# Sheet1.net
KiCad netlist of a schematic drawn in Altium Designer
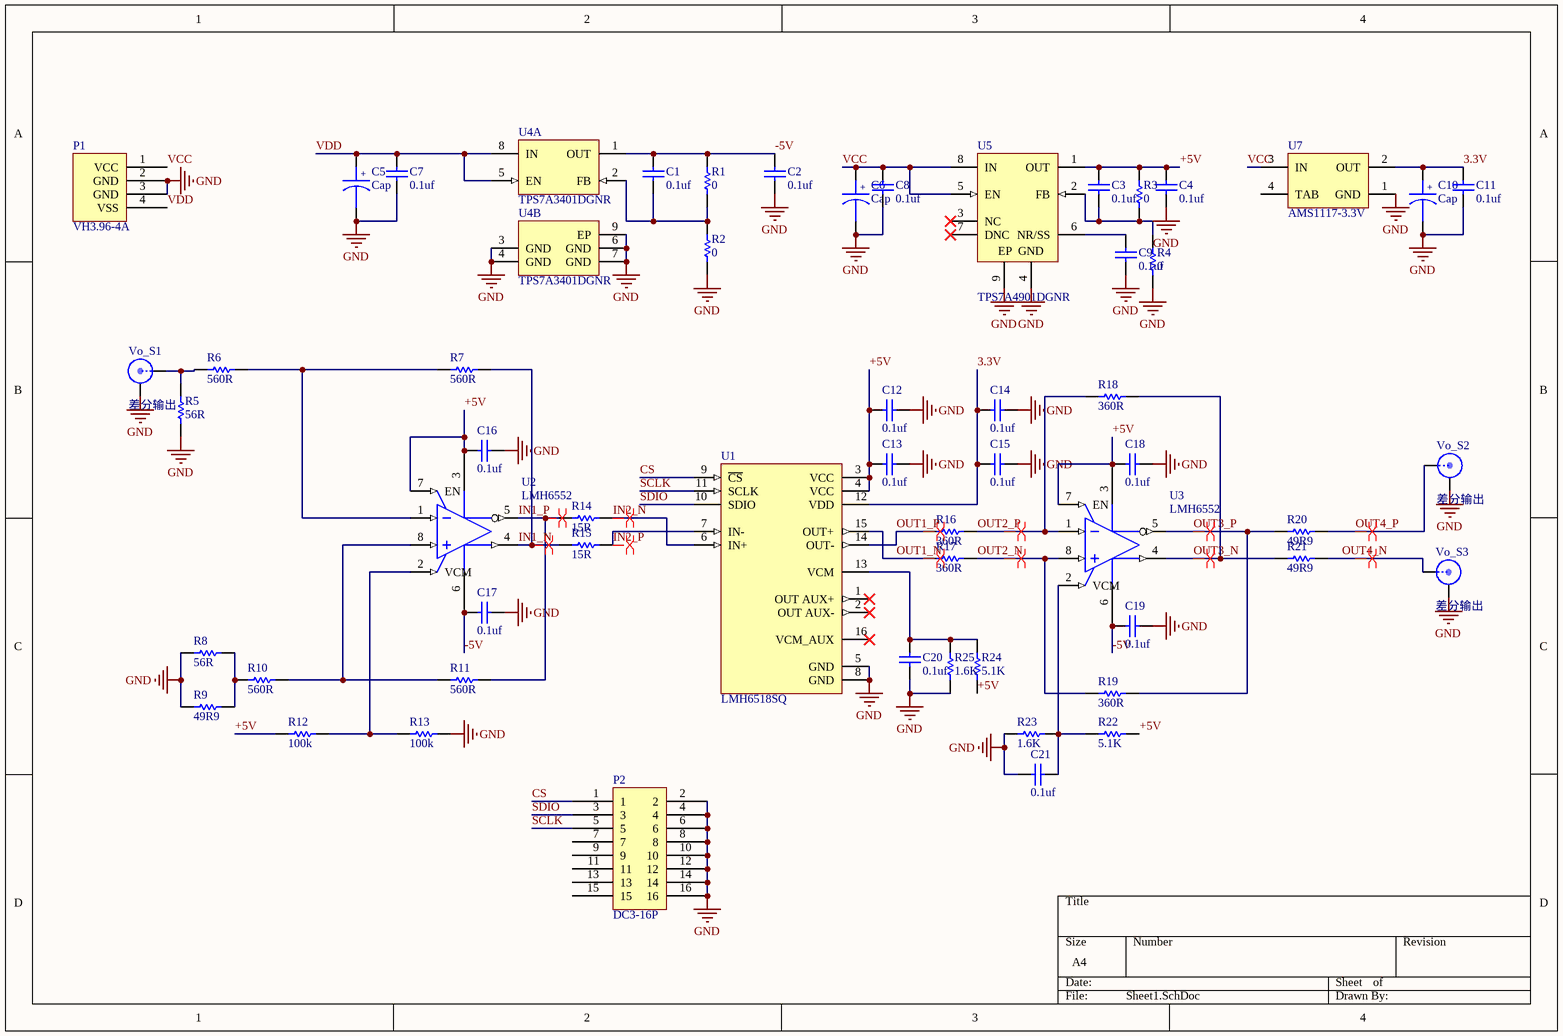
[diagram p0: Sheet1.SchDoc]

(export (version "E")
  (design (tool "Eeschema 10.0.6"))
  (components
    (comp (ref "C1") (value "0.1uf") (footprint "0805") (libsource (lib "Schlib1") (part "Cap")))
    (comp (ref "C2") (value "0.1uf") (footprint "0805") (libsource (lib "Schlib1") (part "Cap")))
    (comp (ref "C3") (value "0.1uf") (footprint "0805") (libsource (lib "Schlib1") (part "Cap")))
    (comp (ref "C4") (value "0.1uf") (footprint "0805") (libsource (lib "Schlib1") (part "Cap")))
    (comp (ref "C5")
      (value "Cap")
      (footprint "7343C-TYPE_D")
      (libsource (lib "Schlib1") (part "Tantalium Cap"))
    )
    (comp (ref "C6")
      (value "Cap")
      (footprint "7343C-TYPE_D")
      (libsource (lib "Schlib1") (part "Tantalium Cap"))
    )
    (comp (ref "C7") (value "0.1uf") (footprint "0805") (libsource (lib "Schlib1") (part "Cap")))
    (comp (ref "C8") (value "0.1uf") (footprint "0805") (libsource (lib "Schlib1") (part "Cap")))
    (comp (ref "C9") (value "0.1uf") (footprint "0805") (libsource (lib "Schlib1") (part "Cap")))
    (comp (ref "C10")
      (value "Cap")
      (footprint "3216C-TYPE_A")
      (libsource (lib "Schlib1") (part "Tantalium Cap"))
    )
    (comp (ref "C11") (value "0.1uf") (footprint "0805") (libsource (lib "Schlib1") (part "Cap")))
    (comp (ref "C12") (value "0.1uf") (footprint "0603C") (libsource (lib "Schlib1") (part "Cap")))
    (comp (ref "C13") (value "0.1uf") (footprint "0603C") (libsource (lib "Schlib1") (part "Cap")))
    (comp (ref "C14") (value "0.1uf") (footprint "0603C") (libsource (lib "Schlib1") (part "Cap")))
    (comp (ref "C15") (value "0.1uf") (footprint "0603C") (libsource (lib "Schlib1") (part "Cap")))
    (comp (ref "C16") (value "0.1uf") (footprint "0805") (libsource (lib "Schlib1") (part "Cap")))
    (comp (ref "C17") (value "0.1uf") (footprint "0805") (libsource (lib "Schlib1") (part "Cap")))
    (comp (ref "C18") (value "0.1uf") (footprint "0805") (libsource (lib "Schlib1") (part "Cap")))
    (comp (ref "C19") (value "0.1uf") (footprint "0805") (libsource (lib "Schlib1") (part "Cap")))
    (comp (ref "C20") (value "0.1uf") (footprint "0603C") (libsource (lib "Schlib1") (part "Cap")))
    (comp (ref "C21") (value "0.1uf") (footprint "0603C") (libsource (lib "Schlib1") (part "Cap")))
    (comp (ref "P1")
      (value "VH3.96-4A")
      (footprint "VH3.96-4P")
      (libsource (lib "Schlib1") (part "VH3.96-4A"))
    )
    (comp (ref "P2") (value "DC3-16P") (footprint "DC3-14P") (libsource (lib "Schlib1") (part "DC3-16P")))
    (comp (ref "R1") (value "0") (footprint "0805") (libsource (lib "Schlib1") (part "Res")))
    (comp (ref "R2") (value "0") (footprint "0805") (libsource (lib "Schlib1") (part "Res")))
    (comp (ref "R3") (value "0") (footprint "0805") (libsource (lib "Schlib1") (part "Res")))
    (comp (ref "R4") (value "0") (footprint "0805") (libsource (lib "Schlib1") (part "Res")))
    (comp (ref "R5") (value "56R") (footprint "0603R") (libsource (lib "Schlib1") (part "Res")))
    (comp (ref "R6") (value "560R") (footprint "0603R") (libsource (lib "Schlib1") (part "Res")))
    (comp (ref "R7") (value "560R") (footprint "0603R") (libsource (lib "Schlib1") (part "Res")))
    (comp (ref "R8") (value "56R") (footprint "0603R") (libsource (lib "Schlib1") (part "Res")))
    (comp (ref "R9") (value "49R9") (footprint "0603R") (libsource (lib "Schlib1") (part "Res")))
    (comp (ref "R10") (value "560R") (footprint "0603R") (libsource (lib "Schlib1") (part "Res")))
    (comp (ref "R11") (value "560R") (footprint "0603R") (libsource (lib "Schlib1") (part "Res")))
    (comp (ref "R12") (value "100k") (footprint "0603R") (libsource (lib "Schlib1") (part "Res")))
    (comp (ref "R13") (value "100k") (footprint "0603R") (libsource (lib "Schlib1") (part "Res")))
    (comp (ref "R14") (value "15R") (footprint "0603R") (libsource (lib "Schlib1") (part "Res")))
    (comp (ref "R15") (value "15R") (footprint "0603R") (libsource (lib "Schlib1") (part "Res")))
    (comp (ref "R16") (value "360R") (footprint "0603R") (libsource (lib "Schlib1") (part "Res")))
    (comp (ref "R17") (value "360R") (footprint "0603R") (libsource (lib "Schlib1") (part "Res")))
    (comp (ref "R18") (value "360R") (footprint "0603R") (libsource (lib "Schlib1") (part "Res")))
    (comp (ref "R19") (value "360R") (footprint "0603R") (libsource (lib "Schlib1") (part "Res")))
    (comp (ref "R20") (value "49R9") (footprint "0603R") (libsource (lib "Schlib1") (part "Res")))
    (comp (ref "R21") (value "49R9") (footprint "0603R") (libsource (lib "Schlib1") (part "Res")))
    (comp (ref "R22") (value "5.1K") (footprint "0603R") (libsource (lib "Schlib1") (part "Res")))
    (comp (ref "R23") (value "1.6K") (footprint "0603R") (libsource (lib "Schlib1") (part "Res")))
    (comp (ref "R24") (value "5.1K") (footprint "0603R") (libsource (lib "Schlib1") (part "Res")))
    (comp (ref "R25") (value "1.6K") (footprint "0603R") (libsource (lib "Schlib1") (part "Res")))
    (comp (ref "U1")
      (value "LMH6518SQ")
      (footprint "SQA16A")
      (description "900 MHz, Digitally Controlled, Variable Gain Amplifier, 16-pin LLP")
      (fields (field (name "PARTNUMBER") "LMH6518") (field (name "MANUFACTURER") "National Semiconductor"))
      (libsource (lib "Schlib1") (part "LMH6518SQ"))
    )
    (comp (ref "U2") (value "LMH6552") (footprint "TI-D8_M") (libsource (lib "Schlib1") (part "LMH6552")))
    (comp (ref "U3") (value "LMH6552") (footprint "TI-D8_M") (libsource (lib "Schlib1") (part "LMH6552")))
    (comp (ref "U4")
      (value "TPS7A3401DGNR")
      (footprint "TI-DGN8-1760X1425TP_N")
      (fields (field (name "MANUFACTURER") "Texas Instruments"))
      (libsource (lib "Schlib1") (part "TPS7A3401DGNR"))
    )
    (comp (ref "U5")
      (value "TPS7A4901DGNR")
      (footprint "TI-DGN8-1760X1425TP_L")
      (fields (field (name "MANUFACTURER") "Texas Instruments"))
      (libsource (lib "Schlib1") (part "TPS7A4901DGNR"))
    )
    (comp (ref "U7")
      (value "AMS1117-3.3V")
      (footprint "SOT-223")
      (libsource (lib "Schlib1") (part "AMS1117-3.3V"))
    )
    (comp (ref "Vo_S1") (value "差分输出") (footprint "SMA-LYING") (libsource (lib "Schlib1") (part "SMA")))
    (comp (ref "Vo_S2") (value "差分输出") (footprint "SMA-LYING") (libsource (lib "Schlib1") (part "SMA")))
    (comp (ref "Vo_S3") (value "差分输出") (footprint "SMA-LYING") (libsource (lib "Schlib1") (part "SMA")))
  )
  (nets
    (net (code "1") (name "/+5V") (class "Default")
      (node (ref "C12") (pin "1") (pinfunction "1_1") (pintype "passive"))
      (node (ref "C13") (pin "1") (pinfunction "1_1") (pintype "passive"))
      (node (ref "C16") (pin "1") (pinfunction "1_1") (pintype "passive"))
      (node (ref "C18") (pin "2") (pinfunction "2_2") (pintype "passive"))
      (node (ref "C3") (pin "2") (pinfunction "2_2") (pintype "passive"))
      (node (ref "C4") (pin "2") (pinfunction "2_2") (pintype "passive"))
      (node (ref "R12") (pin "2") (pinfunction "2_2") (pintype "passive"))
      (node (ref "R22") (pin "1") (pinfunction "1_1") (pintype "passive"))
      (node (ref "R24") (pin "2") (pinfunction "2_2") (pintype "passive"))
      (node (ref "R3") (pin "2") (pinfunction "2_2") (pintype "passive"))
      (node (ref "U1") (pin "3") (pinfunction "VCC_3") (pintype "power_in"))
      (node (ref "U1") (pin "4") (pinfunction "VCC_4") (pintype "power_in"))
      (node (ref "U2") (pin "3") (pinfunction "VCC_3") (pintype "passive"))
      (node (ref "U2") (pin "7") (pinfunction "EN_7") (pintype "input"))
      (node (ref "U3") (pin "3") (pinfunction "VCC_3") (pintype "passive"))
      (node (ref "U3") (pin "7") (pinfunction "EN_7") (pintype "input"))
      (node (ref "U5") (pin "1") (pinfunction "OUT_1") (pintype "power_in"))
    )
    (net (code "2") (name "/-5V") (class "Default")
      (node (ref "C1") (pin "2") (pinfunction "2_2") (pintype "passive"))
      (node (ref "C17") (pin "1") (pinfunction "1_1") (pintype "passive"))
      (node (ref "C19") (pin "2") (pinfunction "2_2") (pintype "passive"))
      (node (ref "C2") (pin "2") (pinfunction "2_2") (pintype "passive"))
      (node (ref "R1") (pin "2") (pinfunction "2_2") (pintype "passive"))
      (node (ref "U2") (pin "6") (pinfunction "VDD_6") (pintype "passive"))
      (node (ref "U3") (pin "6") (pinfunction "VDD_6") (pintype "passive"))
      (node (ref "U4") (pin "1") (pinfunction "OUT_1") (pintype "power_in"))
    )
    (net (code "3") (name "/3.3V") (class "Default")
      (node (ref "C10") (pin "1") (pinfunction "1_1") (pintype "passive"))
      (node (ref "C11") (pin "2") (pinfunction "2_2") (pintype "passive"))
      (node (ref "C14") (pin "1") (pinfunction "1_1") (pintype "passive"))
      (node (ref "C15") (pin "1") (pinfunction "1_1") (pintype "passive"))
      (node (ref "U1") (pin "12") (pinfunction "VDD_12") (pintype "power_in"))
      (node (ref "U7") (pin "2") (pinfunction "OUT_2") (pintype "power_in"))
    )
    (net (code "4") (name "/CS") (class "Default")
      (node (ref "P2") (pin "1") (pinfunction "1_1") (pintype "passive"))
      (node (ref "U1") (pin "9") (pinfunction "~{CS}_9") (pintype "input"))
    )
    (net (code "5") (name "/IN1_N") (class "Default")
      (node (ref "R15") (pin "2") (pinfunction "2_2") (pintype "passive"))
      (node (ref "R7") (pin "1") (pinfunction "1_1") (pintype "passive"))
      (node (ref "U2") (pin "4") (pinfunction "Q_4") (pintype "output"))
    )
    (net (code "6") (name "/IN1_P") (class "Default")
      (node (ref "R11") (pin "1") (pinfunction "1_1") (pintype "passive"))
      (node (ref "R14") (pin "2") (pinfunction "2_2") (pintype "passive"))
      (node (ref "U2") (pin "5") (pinfunction "~{Q}_5") (pintype "output"))
    )
    (net (code "7") (name "/IN2_N") (class "Default")
      (node (ref "R14") (pin "1") (pinfunction "1_1") (pintype "passive"))
      (node (ref "U1") (pin "6") (pinfunction "IN+_6") (pintype "input"))
    )
    (net (code "8") (name "/IN2_P") (class "Default")
      (node (ref "R15") (pin "1") (pinfunction "1_1") (pintype "passive"))
      (node (ref "U1") (pin "7") (pinfunction "IN-_7") (pintype "input"))
    )
    (net (code "9") (name "/OUT1_N") (class "Default")
      (node (ref "R17") (pin "2") (pinfunction "2_2") (pintype "passive"))
      (node (ref "U1") (pin "15") (pinfunction "OUT+_15") (pintype "output"))
    )
    (net (code "10") (name "/OUT1_P") (class "Default")
      (node (ref "R16") (pin "2") (pinfunction "2_2") (pintype "passive"))
      (node (ref "U1") (pin "14") (pinfunction "OUT-_14") (pintype "output"))
    )
    (net (code "11") (name "/OUT2_N") (class "Default")
      (node (ref "R17") (pin "1") (pinfunction "1_1") (pintype "passive"))
      (node (ref "R19") (pin "2") (pinfunction "2_2") (pintype "passive"))
      (node (ref "U3") (pin "8") (pinfunction "VP_8") (pintype "input"))
    )
    (net (code "12") (name "/OUT2_P") (class "Default")
      (node (ref "R16") (pin "1") (pinfunction "1_1") (pintype "passive"))
      (node (ref "R18") (pin "2") (pinfunction "2_2") (pintype "passive"))
      (node (ref "U3") (pin "1") (pinfunction "VN_1") (pintype "input"))
    )
    (net (code "13") (name "/OUT3_N") (class "Default")
      (node (ref "R18") (pin "1") (pinfunction "1_1") (pintype "passive"))
      (node (ref "R21") (pin "1") (pinfunction "1_1") (pintype "passive"))
      (node (ref "U3") (pin "4") (pinfunction "Q_4") (pintype "output"))
    )
    (net (code "14") (name "/OUT3_P") (class "Default")
      (node (ref "R19") (pin "1") (pinfunction "1_1") (pintype "passive"))
      (node (ref "R20") (pin "1") (pinfunction "1_1") (pintype "passive"))
      (node (ref "U3") (pin "5") (pinfunction "~{Q}_5") (pintype "output"))
    )
    (net (code "15") (name "/OUT4_N") (class "Default")
      (node (ref "R21") (pin "2") (pinfunction "2_2") (pintype "passive"))
      (node (ref "Vo_S3") (pin "0") (pinfunction "0_0") (pintype "passive"))
    )
    (net (code "16") (name "/OUT4_P") (class "Default")
      (node (ref "R20") (pin "2") (pinfunction "2_2") (pintype "passive"))
      (node (ref "Vo_S2") (pin "0") (pinfunction "0_0") (pintype "passive"))
    )
    (net (code "17") (name "/SCLK") (class "Default")
      (node (ref "P2") (pin "5") (pinfunction "5_5") (pintype "passive"))
      (node (ref "U1") (pin "11") (pinfunction "SCLK_11") (pintype "input"))
    )
    (net (code "18") (name "/SDIO") (class "Default")
      (node (ref "P2") (pin "3") (pinfunction "3_3") (pintype "passive"))
      (node (ref "U1") (pin "10") (pinfunction "SDIO_10") (pintype "tri_state"))
    )
    (net (code "19") (name "/VCC") (class "Default")
      (node (ref "C6") (pin "1") (pinfunction "1_1") (pintype "passive"))
      (node (ref "C8") (pin "2") (pinfunction "2_2") (pintype "passive"))
      (node (ref "P1") (pin "1") (pinfunction "VCC_1") (pintype "passive"))
      (node (ref "U5") (pin "5") (pinfunction "EN_5") (pintype "input"))
      (node (ref "U5") (pin "8") (pinfunction "IN_8") (pintype "power_in"))
      (node (ref "U7") (pin "3") (pinfunction "IN_3") (pintype "power_in"))
    )
    (net (code "20") (name "/VDD") (class "Default")
      (node (ref "C5") (pin "1") (pinfunction "1_1") (pintype "passive"))
      (node (ref "C7") (pin "2") (pinfunction "2_2") (pintype "passive"))
      (node (ref "P1") (pin "4") (pinfunction "VSS_4") (pintype "passive"))
      (node (ref "U4") (pin "5") (pinfunction "EN_5") (pintype "input"))
      (node (ref "U4") (pin "8") (pinfunction "IN_8") (pintype "power_in"))
    )
    (net (code "21") (name "GND") (class "Default")
      (node (ref "C10") (pin "2") (pinfunction "2_2") (pintype "passive"))
      (node (ref "C11") (pin "1") (pinfunction "1_1") (pintype "passive"))
      (node (ref "C12") (pin "2") (pinfunction "2_2") (pintype "passive"))
      (node (ref "C13") (pin "2") (pinfunction "2_2") (pintype "passive"))
      (node (ref "C14") (pin "2") (pinfunction "2_2") (pintype "passive"))
      (node (ref "C15") (pin "2") (pinfunction "2_2") (pintype "passive"))
      (node (ref "C16") (pin "2") (pinfunction "2_2") (pintype "passive"))
      (node (ref "C17") (pin "2") (pinfunction "2_2") (pintype "passive"))
      (node (ref "C18") (pin "1") (pinfunction "1_1") (pintype "passive"))
      (node (ref "C19") (pin "1") (pinfunction "1_1") (pintype "passive"))
      (node (ref "C2") (pin "1") (pinfunction "1_1") (pintype "passive"))
      (node (ref "C20") (pin "1") (pinfunction "1_1") (pintype "passive"))
      (node (ref "C21") (pin "2") (pinfunction "2_2") (pintype "passive"))
      (node (ref "C4") (pin "1") (pinfunction "1_1") (pintype "passive"))
      (node (ref "C5") (pin "2") (pinfunction "2_2") (pintype "passive"))
      (node (ref "C6") (pin "2") (pinfunction "2_2") (pintype "passive"))
      (node (ref "C7") (pin "1") (pinfunction "1_1") (pintype "passive"))
      (node (ref "C8") (pin "1") (pinfunction "1_1") (pintype "passive"))
      (node (ref "C9") (pin "1") (pinfunction "1_1") (pintype "passive"))
      (node (ref "P1") (pin "2") (pinfunction "GND_2") (pintype "passive"))
      (node (ref "P1") (pin "3") (pinfunction "GND_3") (pintype "passive"))
      (node (ref "P2") (pin "10") (pinfunction "10_10") (pintype "passive"))
      (node (ref "P2") (pin "12") (pinfunction "12_12") (pintype "passive"))
      (node (ref "P2") (pin "14") (pinfunction "14_14") (pintype "passive"))
      (node (ref "P2") (pin "16") (pinfunction "16_16") (pintype "passive"))
      (node (ref "P2") (pin "2") (pinfunction "2_2") (pintype "passive"))
      (node (ref "P2") (pin "4") (pinfunction "4_4") (pintype "passive"))
      (node (ref "P2") (pin "6") (pinfunction "6_6") (pintype "passive"))
      (node (ref "P2") (pin "8") (pinfunction "8_8") (pintype "passive"))
      (node (ref "R13") (pin "1") (pinfunction "1_1") (pintype "passive"))
      (node (ref "R2") (pin "1") (pinfunction "1_1") (pintype "passive"))
      (node (ref "R23") (pin "2") (pinfunction "2_2") (pintype "passive"))
      (node (ref "R25") (pin "2") (pinfunction "2_2") (pintype "passive"))
      (node (ref "R4") (pin "1") (pinfunction "1_1") (pintype "passive"))
      (node (ref "R5") (pin "1") (pinfunction "1_1") (pintype "passive"))
      (node (ref "R8") (pin "2") (pinfunction "2_2") (pintype "passive"))
      (node (ref "R9") (pin "2") (pinfunction "2_2") (pintype "passive"))
      (node (ref "U1") (pin "5") (pinfunction "GND_5") (pintype "power_in"))
      (node (ref "U1") (pin "8") (pinfunction "GND_8") (pintype "power_in"))
      (node (ref "U4") (pin "3") (pinfunction "GND_3") (pintype "power_in"))
      (node (ref "U4") (pin "4") (pinfunction "GND_4") (pintype "power_in"))
      (node (ref "U4") (pin "6") (pinfunction "GND_6") (pintype "power_in"))
      (node (ref "U4") (pin "7") (pinfunction "GND_7") (pintype "power_in"))
      (node (ref "U4") (pin "9") (pinfunction "EP_9") (pintype "power_in"))
      (node (ref "U5") (pin "4") (pinfunction "GND_4") (pintype "power_in"))
      (node (ref "U5") (pin "9") (pinfunction "EP_9") (pintype "power_in"))
      (node (ref "U7") (pin "1") (pinfunction "GND_1") (pintype "power_in"))
      (node (ref "Vo_S1") (pin "1") (pinfunction "1_1") (pintype "passive"))
      (node (ref "Vo_S2") (pin "1") (pinfunction "1_1") (pintype "passive"))
      (node (ref "Vo_S3") (pin "1") (pinfunction "1_1") (pintype "passive"))
    )
    (net (code "22") (name "Net-(R5-Pad2)") (class "Default")
      (node (ref "R5") (pin "2") (pinfunction "2_2") (pintype "passive"))
      (node (ref "R6") (pin "2") (pinfunction "2_2") (pintype "passive"))
      (node (ref "Vo_S1") (pin "0") (pinfunction "0_0") (pintype "passive"))
    )
    (net (code "23") (name "Net-(R10-Pad2)") (class "Default")
      (node (ref "R10") (pin "2") (pinfunction "2_2") (pintype "passive"))
      (node (ref "R8") (pin "1") (pinfunction "1_1") (pintype "passive"))
      (node (ref "R9") (pin "1") (pinfunction "1_1") (pintype "passive"))
    )
    (net (code "24") (name "Net-(U1-VCM)") (class "Default")
      (node (ref "C20") (pin "2") (pinfunction "2_2") (pintype "passive"))
      (node (ref "R24") (pin "1") (pinfunction "1_1") (pintype "passive"))
      (node (ref "R25") (pin "1") (pinfunction "1_1") (pintype "passive"))
      (node (ref "U1") (pin "13") (pinfunction "VCM_13") (pintype "passive"))
    )
    (net (code "25") (name "Net-(U2-VCM)") (class "Default")
      (node (ref "R12") (pin "1") (pinfunction "1_1") (pintype "passive"))
      (node (ref "R13") (pin "2") (pinfunction "2_2") (pintype "passive"))
      (node (ref "U2") (pin "2") (pinfunction "VCM_2") (pintype "input"))
    )
    (net (code "26") (name "Net-(U2-VN)") (class "Default")
      (node (ref "R6") (pin "1") (pinfunction "1_1") (pintype "passive"))
      (node (ref "R7") (pin "2") (pinfunction "2_2") (pintype "passive"))
      (node (ref "U2") (pin "1") (pinfunction "VN_1") (pintype "input"))
    )
    (net (code "27") (name "Net-(U2-VP)") (class "Default")
      (node (ref "R10") (pin "1") (pinfunction "1_1") (pintype "passive"))
      (node (ref "R11") (pin "2") (pinfunction "2_2") (pintype "passive"))
      (node (ref "U2") (pin "8") (pinfunction "VP_8") (pintype "input"))
    )
    (net (code "28") (name "Net-(U3-VCM)") (class "Default")
      (node (ref "C21") (pin "1") (pinfunction "1_1") (pintype "passive"))
      (node (ref "R22") (pin "2") (pinfunction "2_2") (pintype "passive"))
      (node (ref "R23") (pin "1") (pinfunction "1_1") (pintype "passive"))
      (node (ref "U3") (pin "2") (pinfunction "VCM_2") (pintype "input"))
    )
    (net (code "29") (name "Net-(U4A-FB)") (class "Default")
      (node (ref "C1") (pin "1") (pinfunction "1_1") (pintype "passive"))
      (node (ref "R1") (pin "1") (pinfunction "1_1") (pintype "passive"))
      (node (ref "R2") (pin "2") (pinfunction "2_2") (pintype "passive"))
      (node (ref "U4") (pin "2") (pinfunction "FB_2") (pintype "input"))
    )
    (net (code "30") (name "Net-(U5-FB)") (class "Default")
      (node (ref "C3") (pin "1") (pinfunction "1_1") (pintype "passive"))
      (node (ref "R3") (pin "1") (pinfunction "1_1") (pintype "passive"))
      (node (ref "R4") (pin "2") (pinfunction "2_2") (pintype "passive"))
      (node (ref "U5") (pin "2") (pinfunction "FB_2") (pintype "input"))
    )
    (net (code "31") (name "Net-(U5-NR{slash}SS)") (class "Default")
      (node (ref "C9") (pin "2") (pinfunction "2_2") (pintype "passive"))
      (node (ref "U5") (pin "6") (pinfunction "NR/SS_6") (pintype "passive"))
    )
    (net (code "32") (name "unconnected-(P2-Pad7)") (class "Default")
      (node (ref "P2") (pin "7") (pinfunction "7_7") (pintype "passive"))
    )
    (net (code "33") (name "unconnected-(P2-Pad9)") (class "Default")
      (node (ref "P2") (pin "9") (pinfunction "9_9") (pintype "passive"))
    )
    (net (code "34") (name "unconnected-(P2-Pad11)") (class "Default")
      (node (ref "P2") (pin "11") (pinfunction "11_11") (pintype "passive"))
    )
    (net (code "35") (name "unconnected-(P2-Pad13)") (class "Default")
      (node (ref "P2") (pin "13") (pinfunction "13_13") (pintype "passive"))
    )
    (net (code "36") (name "unconnected-(P2-Pad15)") (class "Default")
      (node (ref "P2") (pin "15") (pinfunction "15_15") (pintype "passive"))
    )
    (net (code "37") (name "unconnected-(U1-OUT_AUX+-Pad1)") (class "Default")
      (node (ref "U1") (pin "1") (pinfunction "OUT_AUX+_1") (pintype "output+no_connect"))
    )
    (net (code "38") (name "unconnected-(U1-OUT_AUX--Pad2)") (class "Default")
      (node (ref "U1") (pin "2") (pinfunction "OUT_AUX-_2") (pintype "output+no_connect"))
    )
    (net (code "39") (name "unconnected-(U1-VCM_AUX-Pad16)") (class "Default")
      (node (ref "U1") (pin "16") (pinfunction "VCM_AUX_16") (pintype "passive+no_connect"))
    )
    (net (code "40") (name "unconnected-(U5-DNC-Pad7)") (class "Default")
      (node (ref "U5") (pin "7") (pinfunction "DNC_7") (pintype "passive+no_connect"))
    )
    (net (code "41") (name "unconnected-(U5-NC-Pad3)") (class "Default")
      (node (ref "U5") (pin "3") (pinfunction "NC_3") (pintype "passive+no_connect"))
    )
    (net (code "42") (name "unconnected-(U7-TAB-Pad4)") (class "Default")
      (node (ref "U7") (pin "4") (pinfunction "TAB_4") (pintype "power_in"))
    )
  )
)
